# SensWear_MPU.net
KiCad netlist of a schematic drawn in Altium Designer
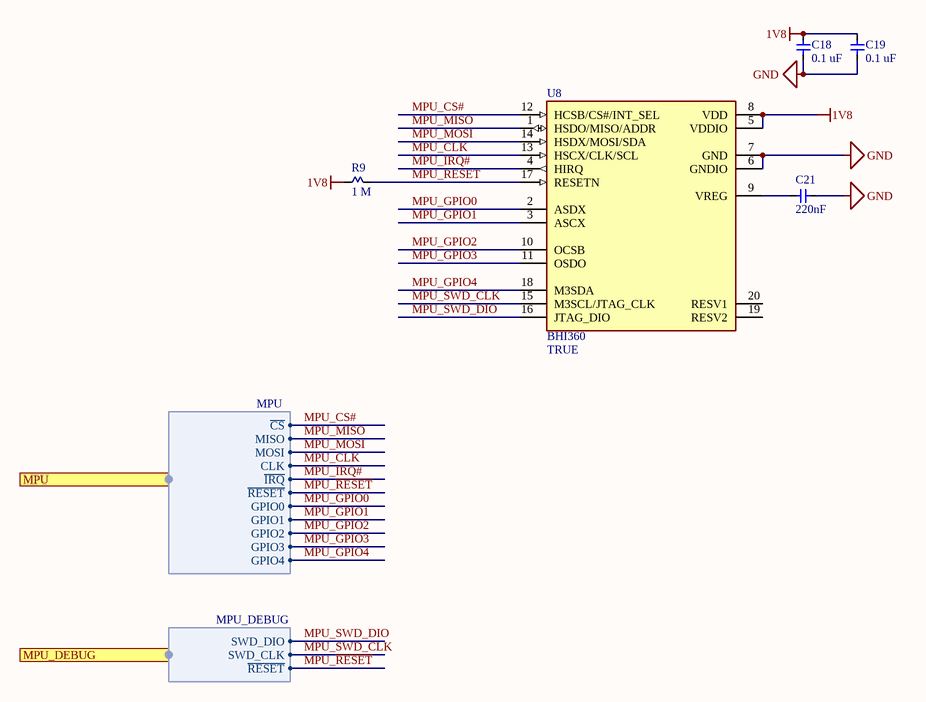
[diagram p0: SensWear_MPU.SchDoc]

(export (version "E")
  (design (tool "Eeschema 10.0.6"))
  (components
    (comp (ref "C18")
      (value "0.1 uF")
      (footprint "CAPC1005X05N")
      (description "CAP CER 0.1UF 16V X5R 0402")
      (fields
        (field (name "MANUFACTURER") "Murata Electronics")
        (field (name "MANUFACTURER PART NUMBER") "GRM155R61C104KA88D")
      )
      (libsource (lib "OpenRingComponents") (part "GRM155R61C104KA88D"))
    )
    (comp (ref "C19")
      (value "0.1 uF")
      (footprint "CAPC1005X05N")
      (description "CAP CER 0.1UF 16V X5R 0402")
      (fields
        (field (name "MANUFACTURER") "Murata Electronics")
        (field (name "MANUFACTURER PART NUMBER") "GRM155R61C104KA88D")
      )
      (libsource (lib "OpenRingComponents") (part "GRM155R61C104KA88D"))
    )
    (comp (ref "C21")
      (value "220nF")
      (footprint "CAPC1005X05N")
      (description "CAP CER 0.22UF 16V X5R 0402")
      (fields
        (field (name "MANUFACTURER") "Murata")
        (field (name "MANUFACTURER PART NUMBER") "GRM155R61C224KA12D")
      )
      (libsource (lib "OpenRingComponents") (part "GRM155R61C224KA12D"))
    )
    (comp (ref "R9")
      (value "1 M")
      (footprint "RESC1005X04N")
      (description "RES SMD 1M OHM 1% 1/10W 0402")
      (fields
        (field (name "MANUFACTURER") "Panasonic Electronic Components")
        (field (name "MANUFACTURER PART NUMBER") "ERJ-2RKF1004X")
      )
      (libsource (lib "OpenRingComponents") (part "ERJ-2RKF1004X"))
    )
    (comp (ref "U8")
      (value "BHI360")
      (footprint "BHI360")
      (description "Programmable smart sensor combining accelerometer, gyroscope and fusion software")
      (fields (field (name "MANUFACTURER") "Bosch Tools") (field (name "CHECKED") "TRUE"))
      (libsource (lib "ICs") (part "BHI360"))
    )
  )
  (nets
    (net (code "3") (name "/MPU_CLK") (class "Default")
      (node (ref "U8") (pin "13") (pinfunction "HSCX/CLK/SCL_13") (pintype "input"))
    )
    (net (code "4") (name "/MPU_CS#") (class "Default")
      (node (ref "U8") (pin "12") (pinfunction "HCSB/CS#/INT_SEL_12") (pintype "input"))
    )
    (net (code "5") (name "/MPU_GPIO0") (class "Default")
      (node (ref "U8") (pin "2") (pinfunction "ASDX_2") (pintype "passive"))
    )
    (net (code "6") (name "/MPU_GPIO1") (class "Default")
      (node (ref "U8") (pin "3") (pinfunction "ASCX_3") (pintype "passive"))
    )
    (net (code "7") (name "/MPU_GPIO2") (class "Default")
      (node (ref "U8") (pin "10") (pinfunction "OCSB_10") (pintype "passive"))
    )
    (net (code "8") (name "/MPU_GPIO3") (class "Default")
      (node (ref "U8") (pin "11") (pinfunction "OSDO_11") (pintype "passive"))
    )
    (net (code "9") (name "/MPU_GPIO4") (class "Default")
      (node (ref "U8") (pin "18") (pinfunction "M3SDA_18") (pintype "passive"))
    )
    (net (code "10") (name "/MPU_IRQ#") (class "Default")
      (node (ref "U8") (pin "4") (pinfunction "HIRQ_4") (pintype "output"))
    )
    (net (code "11") (name "/MPU_MISO") (class "Default")
      (node (ref "U8") (pin "1") (pinfunction "HSDO/MISO/ADDR_1") (pintype "bidirectional"))
    )
    (net (code "12") (name "/MPU_MOSI") (class "Default")
      (node (ref "U8") (pin "14") (pinfunction "HSDX/MOSI/SDA_14") (pintype "input"))
    )
    (net (code "13") (name "/MPU_SWD_CLK") (class "Default")
      (node (ref "U8") (pin "15") (pinfunction "M3SCL/JTAG_CLK_15") (pintype "passive"))
    )
    (net (code "14") (name "/MPU_SWD_DIO") (class "Default")
      (node (ref "U8") (pin "16") (pinfunction "JTAG_DIO_16") (pintype "passive"))
    )
    (net (code "15") (name "/MPU_~{RESET}") (class "Default")
      (node (ref "R9") (pin "2") (pinfunction "2_2") (pintype "passive"))
      (node (ref "U8") (pin "17") (pinfunction "RESETN_17") (pintype "input"))
    )
    (net (code "18") (name "1V8") (class "Default")
      (node (ref "C18") (pin "2") (pinfunction "2_2") (pintype "passive"))
      (node (ref "C19") (pin "2") (pinfunction "2_2") (pintype "passive"))
      (node (ref "R9") (pin "1") (pinfunction "1_1") (pintype "passive"))
      (node (ref "U8") (pin "5") (pinfunction "VDDIO_5") (pintype "passive"))
      (node (ref "U8") (pin "8") (pinfunction "VDD_8") (pintype "passive"))
    )
    (net (code "19") (name "GND") (class "Default")
      (node (ref "C18") (pin "1") (pinfunction "1_1") (pintype "passive"))
      (node (ref "C19") (pin "1") (pinfunction "1_1") (pintype "passive"))
      (node (ref "C21") (pin "2") (pinfunction "2_2") (pintype "passive"))
      (node (ref "U8") (pin "6") (pinfunction "GNDIO_6") (pintype "passive"))
      (node (ref "U8") (pin "7") (pinfunction "GND_7") (pintype "passive"))
    )
    (net (code "20") (name "Net-(U8-VREG)") (class "Default")
      (node (ref "C21") (pin "1") (pinfunction "1_1") (pintype "passive"))
      (node (ref "U8") (pin "9") (pinfunction "VREG_9") (pintype "passive"))
    )
    (net (code "21") (name "unconnected-(U8-RESV1-Pad20)") (class "Default")
      (node (ref "U8") (pin "20") (pinfunction "RESV1_20") (pintype "passive"))
    )
    (net (code "22") (name "unconnected-(U8-RESV2-Pad19)") (class "Default")
      (node (ref "U8") (pin "19") (pinfunction "RESV2_19") (pintype "passive"))
    )
  )
)
